# 5V-REG.net
KiCad netlist of a schematic drawn in Altium Designer
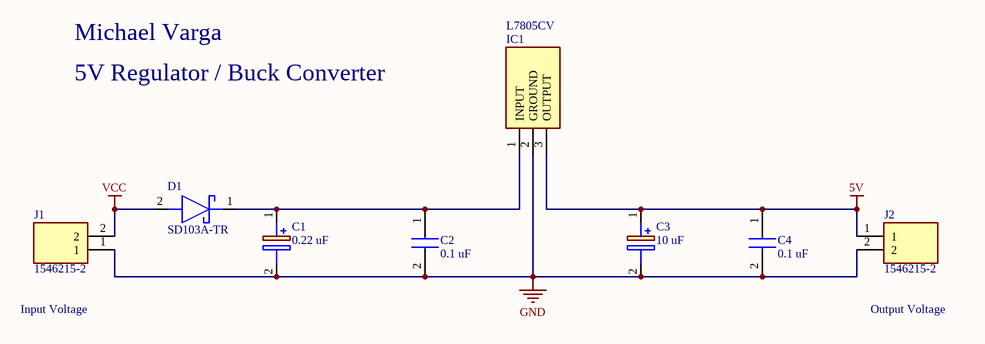
[diagram p0: 5V-REG.SchDoc]

(export (version "E")
  (design (tool "Eeschema 10.0.6"))
  (components
    (comp (ref "C1")
      (value "0.22 uF")
      (footprint "SamacSys:CAPPRD200W52D500H1250")
      (description "Capacitor Polarised")
      (fields
        (field (name "MANUFACTURER_PART_NUMBER") "860010772002")
        (field (name "MOUSER PART NUMBER") "710-860010772002")
      )
      (libsource (lib "*") (part "860010772002"))
    )
    (comp (ref "C2")
      (value "0.1 uF")
      (footprint "SamacSys:RDER71E104K0P1H03B")
      (description "Capacitor")
      (fields
        (field (name "MANUFACTURER_PART_NUMBER") "RDER71E104K0P1H03B")
        (field (name "MOUSER PART NUMBER") "81-RDER71E104K0P1H3B")
      )
      (libsource (lib "*") (part "RDER71E104K0P1H03B"))
    )
    (comp (ref "C3")
      (value "10 uF")
      (footprint "SamacSys:CAPPRD200W55D500H1250")
      (description "Capacitor Polarised")
      (fields
        (field (name "MANUFACTURER_PART_NUMBER") "EEU-FR1H100")
        (field (name "MOUSER PART NUMBER") "667-EEU-FR1H100")
      )
      (libsource (lib "*") (part "EEU-FR1H100"))
    )
    (comp (ref "C4")
      (value "0.1 uF")
      (footprint "SamacSys:RDER71E104K0P1H03B")
      (description "Capacitor")
      (fields
        (field (name "MANUFACTURER_PART_NUMBER") "RDER71E104K0P1H03B")
        (field (name "MOUSER PART NUMBER") "81-RDER71E104K0P1H3B")
      )
      (libsource (lib "*") (part "RDER71E104K0P1H03B"))
    )
    (comp (ref "D1")
      (value "SD103A-TR")
      (footprint "SamacSys:DIOAD950W60L350D150")
      (description "Schottky Diode")
      (fields (field (name "MOUSER PART NUMBER") "625-SD103A"))
      (libsource (lib "*") (part "SD103A-TR"))
    )
    (comp (ref "IC1")
      (value "L7805CV")
      (footprint "SamacSys:TO255P460X1020X2008-3P")
      (description "Integrated Circuit")
      (fields (field (name "MOUSER PART NUMBER") "511-L7805CV"))
      (libsource (lib "*") (part "L7805CV"))
    )
    (comp (ref "J1")
      (value "1546215-2")
      (footprint "SamacSys:15462152")
      (description "Connector")
      (fields (field (name "MOUSER PART NUMBER") "571-1546215-2"))
      (libsource (lib "*") (part "1546215-2"))
    )
    (comp (ref "J2")
      (value "1546215-2")
      (footprint "SamacSys:15462152")
      (description "Connector")
      (fields (field (name "MOUSER PART NUMBER") "571-1546215-2"))
      (libsource (lib "") (part "1546215-2_1"))
    )
  )
  (nets
    (net (code "1") (name "5V") (class "Default")
      (node (ref "C3") (pin "1") (pinfunction "+_1") (pintype "power_in"))
      (node (ref "C4") (pin "1") (pinfunction "1_1") (pintype "passive"))
      (node (ref "IC1") (pin "3") (pinfunction "OUTPUT_3") (pintype "passive"))
      (node (ref "J2") (pin "1") (pinfunction "1_1") (pintype "passive"))
    )
    (net (code "2") (name "GND") (class "Default")
      (node (ref "C1") (pin "2") (pinfunction "-_2") (pintype "passive"))
      (node (ref "C2") (pin "2") (pinfunction "2_2") (pintype "passive"))
      (node (ref "C3") (pin "2") (pinfunction "-_2") (pintype "power_in"))
      (node (ref "C4") (pin "2") (pinfunction "2_2") (pintype "passive"))
      (node (ref "IC1") (pin "2") (pinfunction "GROUND_2") (pintype "passive"))
      (node (ref "J1") (pin "1") (pinfunction "1_1") (pintype "passive"))
      (node (ref "J2") (pin "2") (pinfunction "2_2") (pintype "passive"))
    )
    (net (code "3") (name "Net-(C1-+)") (class "Default")
      (node (ref "C1") (pin "1") (pinfunction "+_1") (pintype "passive"))
      (node (ref "C2") (pin "1") (pinfunction "1_1") (pintype "passive"))
      (node (ref "D1") (pin "1") (pinfunction "K_1") (pintype "passive"))
      (node (ref "IC1") (pin "1") (pinfunction "INPUT_1") (pintype "passive"))
    )
    (net (code "4") (name "VCC") (class "Default")
      (node (ref "D1") (pin "2") (pinfunction "A_2") (pintype "passive"))
      (node (ref "J1") (pin "2") (pinfunction "2_2") (pintype "passive"))
    )
  )
)
